# neojoint-2way.net
KiCad netlist of a schematic drawn in EAGLE
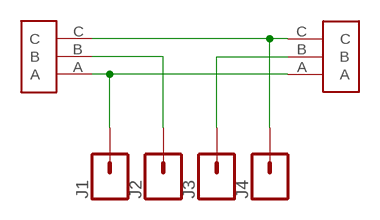
[diagram p0: schematic, sheet 1]

(export (version "E")
  (design (tool "Eeschema 10.0.6"))
  (components
    (comp (ref "J1")
      (value "CONN_01")
      (footprint "eagle-import:1X01")
      (libsource (lib "eagle-import") (part "CONN_01"))
    )
    (comp (ref "J2")
      (value "CONN_01")
      (footprint "eagle-import:1X01")
      (libsource (lib "eagle-import") (part "CONN_01"))
    )
    (comp (ref "J3")
      (value "CONN_01")
      (footprint "eagle-import:1X01")
      (libsource (lib "eagle-import") (part "CONN_01"))
    )
    (comp (ref "J4")
      (value "CONN_01")
      (footprint "eagle-import:1X01")
      (libsource (lib "eagle-import") (part "CONN_01"))
    )
    (comp (ref "U$1")
      (value "LED_STRIP_3P")
      (footprint "eagle-import:LEDSTRIP-3P")
      (libsource (lib "eagle-import") (part "LED_STRIP_3P"))
    )
    (comp (ref "U$2")
      (value "LED_STRIP_3P")
      (footprint "eagle-import:LEDSTRIP-3P")
      (libsource (lib "eagle-import") (part "LED_STRIP_3P"))
    )
  )
  (nets
    (net (code "1") (name "Net-(J1-Pad1)") (class "Default")
      (node (ref "J1") (pin "1") (pinfunction "1_1") (pintype "passive"))
      (node (ref "U$1") (pin "A") (pinfunction "A_A") (pintype "bidirectional"))
      (node (ref "U$2") (pin "A") (pinfunction "A_A") (pintype "bidirectional"))
    )
    (net (code "2") (name "Net-(J2-Pad1)") (class "Default")
      (node (ref "J2") (pin "1") (pinfunction "1_1") (pintype "passive"))
      (node (ref "U$2") (pin "B") (pinfunction "B_B") (pintype "bidirectional"))
    )
    (net (code "3") (name "Net-(J3-Pad1)") (class "Default")
      (node (ref "J3") (pin "1") (pinfunction "1_1") (pintype "passive"))
      (node (ref "U$1") (pin "B") (pinfunction "B_B") (pintype "bidirectional"))
    )
    (net (code "4") (name "Net-(J4-Pad1)") (class "Default")
      (node (ref "J4") (pin "1") (pinfunction "1_1") (pintype "passive"))
      (node (ref "U$1") (pin "C") (pinfunction "C_C") (pintype "bidirectional"))
      (node (ref "U$2") (pin "C") (pinfunction "C_C") (pintype "bidirectional"))
    )
  )
)
